# Interconnect_Splice.net
KiCad netlist of a schematic drawn in EAGLE
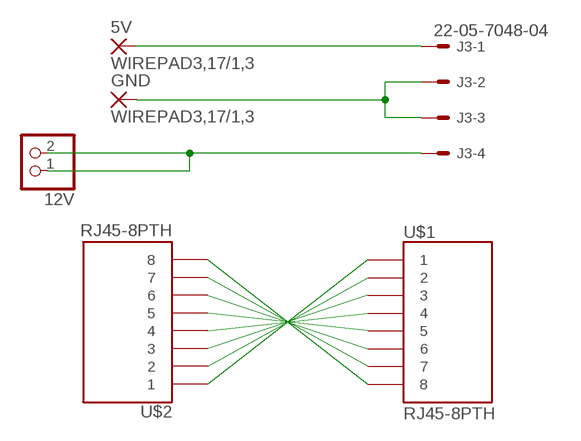
[diagram p0: schematic, sheet 1]

(export (version "E")
  (design (tool "Eeschema 10.0.6"))
  (components
    (comp (ref "5V")
      (value "WIREPAD3,17/1,3")
      (footprint "eagle-import:3,17_1,3")
      (libsource (lib "eagle-import") (part "WIREPAD3,17/1,3"))
    )
    (comp (ref "12V")
      (value "PINHD-1X2/90")
      (footprint "eagle-import:1X02_90")
      (libsource (lib "eagle-import") (part "PINHD-1X2/90"))
    )
    (comp (ref "GND")
      (value "WIREPAD3,17/1,3")
      (footprint "eagle-import:3,17_1,3")
      (libsource (lib "eagle-import") (part "WIREPAD3,17/1,3"))
    )
    (comp (ref "J3")
      (value "22-05-7048-04")
      (footprint "eagle-import:7395-04")
      (libsource (lib "eagle-import") (part "22-?-0405-7048"))
    )
    (comp (ref "U$1")
      (value "RJ45-8PTH")
      (footprint "eagle-import:RJ45-8")
      (libsource (lib "eagle-import") (part "RJ45-8PTH"))
    )
    (comp (ref "U$2")
      (value "RJ45-8PTH")
      (footprint "eagle-import:RJ45-8")
      (libsource (lib "eagle-import") (part "RJ45-8PTH"))
    )
  )
  (nets
    (net (code "1") (name "Net-(5V-P)") (class "Default")
      (node (ref "5V") (pin "1") (pinfunction "P_1") (pintype "passive"))
      (node (ref "J3") (pin "1") (pinfunction "S_1") (pintype "passive"))
    )
    (net (code "2") (name "Net-(GND-P)") (class "Default")
      (node (ref "GND") (pin "1") (pinfunction "P_1") (pintype "passive"))
      (node (ref "J3") (pin "2") (pinfunction "S_2") (pintype "passive"))
      (node (ref "J3") (pin "3") (pinfunction "S_3") (pintype "passive"))
    )
    (net (code "3") (name "Net-(J3D-S)") (class "Default")
      (node (ref "12V") (pin "1") (pinfunction "1_1") (pintype "passive"))
      (node (ref "12V") (pin "2") (pinfunction "2_2") (pintype "passive"))
      (node (ref "J3") (pin "4") (pinfunction "S_4") (pintype "passive"))
    )
    (net (code "4") (name "Net-(U$1-Pad1)") (class "Default")
      (node (ref "U$1") (pin "1") (pinfunction "1_1") (pintype "bidirectional"))
      (node (ref "U$2") (pin "1") (pinfunction "1_1") (pintype "bidirectional"))
    )
    (net (code "5") (name "Net-(U$1-Pad2)") (class "Default")
      (node (ref "U$1") (pin "2") (pinfunction "2_2") (pintype "bidirectional"))
      (node (ref "U$2") (pin "2") (pinfunction "2_2") (pintype "bidirectional"))
    )
    (net (code "6") (name "Net-(U$1-Pad3)") (class "Default")
      (node (ref "U$1") (pin "3") (pinfunction "3_3") (pintype "bidirectional"))
      (node (ref "U$2") (pin "3") (pinfunction "3_3") (pintype "bidirectional"))
    )
    (net (code "7") (name "Net-(U$1-Pad4)") (class "Default")
      (node (ref "U$1") (pin "4") (pinfunction "4_4") (pintype "bidirectional"))
      (node (ref "U$2") (pin "4") (pinfunction "4_4") (pintype "bidirectional"))
    )
    (net (code "8") (name "Net-(U$1-Pad5)") (class "Default")
      (node (ref "U$1") (pin "5") (pinfunction "5_5") (pintype "bidirectional"))
      (node (ref "U$2") (pin "5") (pinfunction "5_5") (pintype "bidirectional"))
    )
    (net (code "9") (name "Net-(U$1-Pad6)") (class "Default")
      (node (ref "U$1") (pin "6") (pinfunction "6_6") (pintype "bidirectional"))
      (node (ref "U$2") (pin "6") (pinfunction "6_6") (pintype "bidirectional"))
    )
    (net (code "10") (name "Net-(U$1-Pad7)") (class "Default")
      (node (ref "U$1") (pin "7") (pinfunction "7_7") (pintype "bidirectional"))
      (node (ref "U$2") (pin "7") (pinfunction "7_7") (pintype "bidirectional"))
    )
    (net (code "11") (name "Net-(U$1-Pad8)") (class "Default")
      (node (ref "U$1") (pin "8") (pinfunction "8_8") (pintype "bidirectional"))
      (node (ref "U$2") (pin "8") (pinfunction "8_8") (pintype "bidirectional"))
    )
  )
)
